# small_tv_screen.net
KiCad netlist of a schematic drawn in EasyEDA Pro
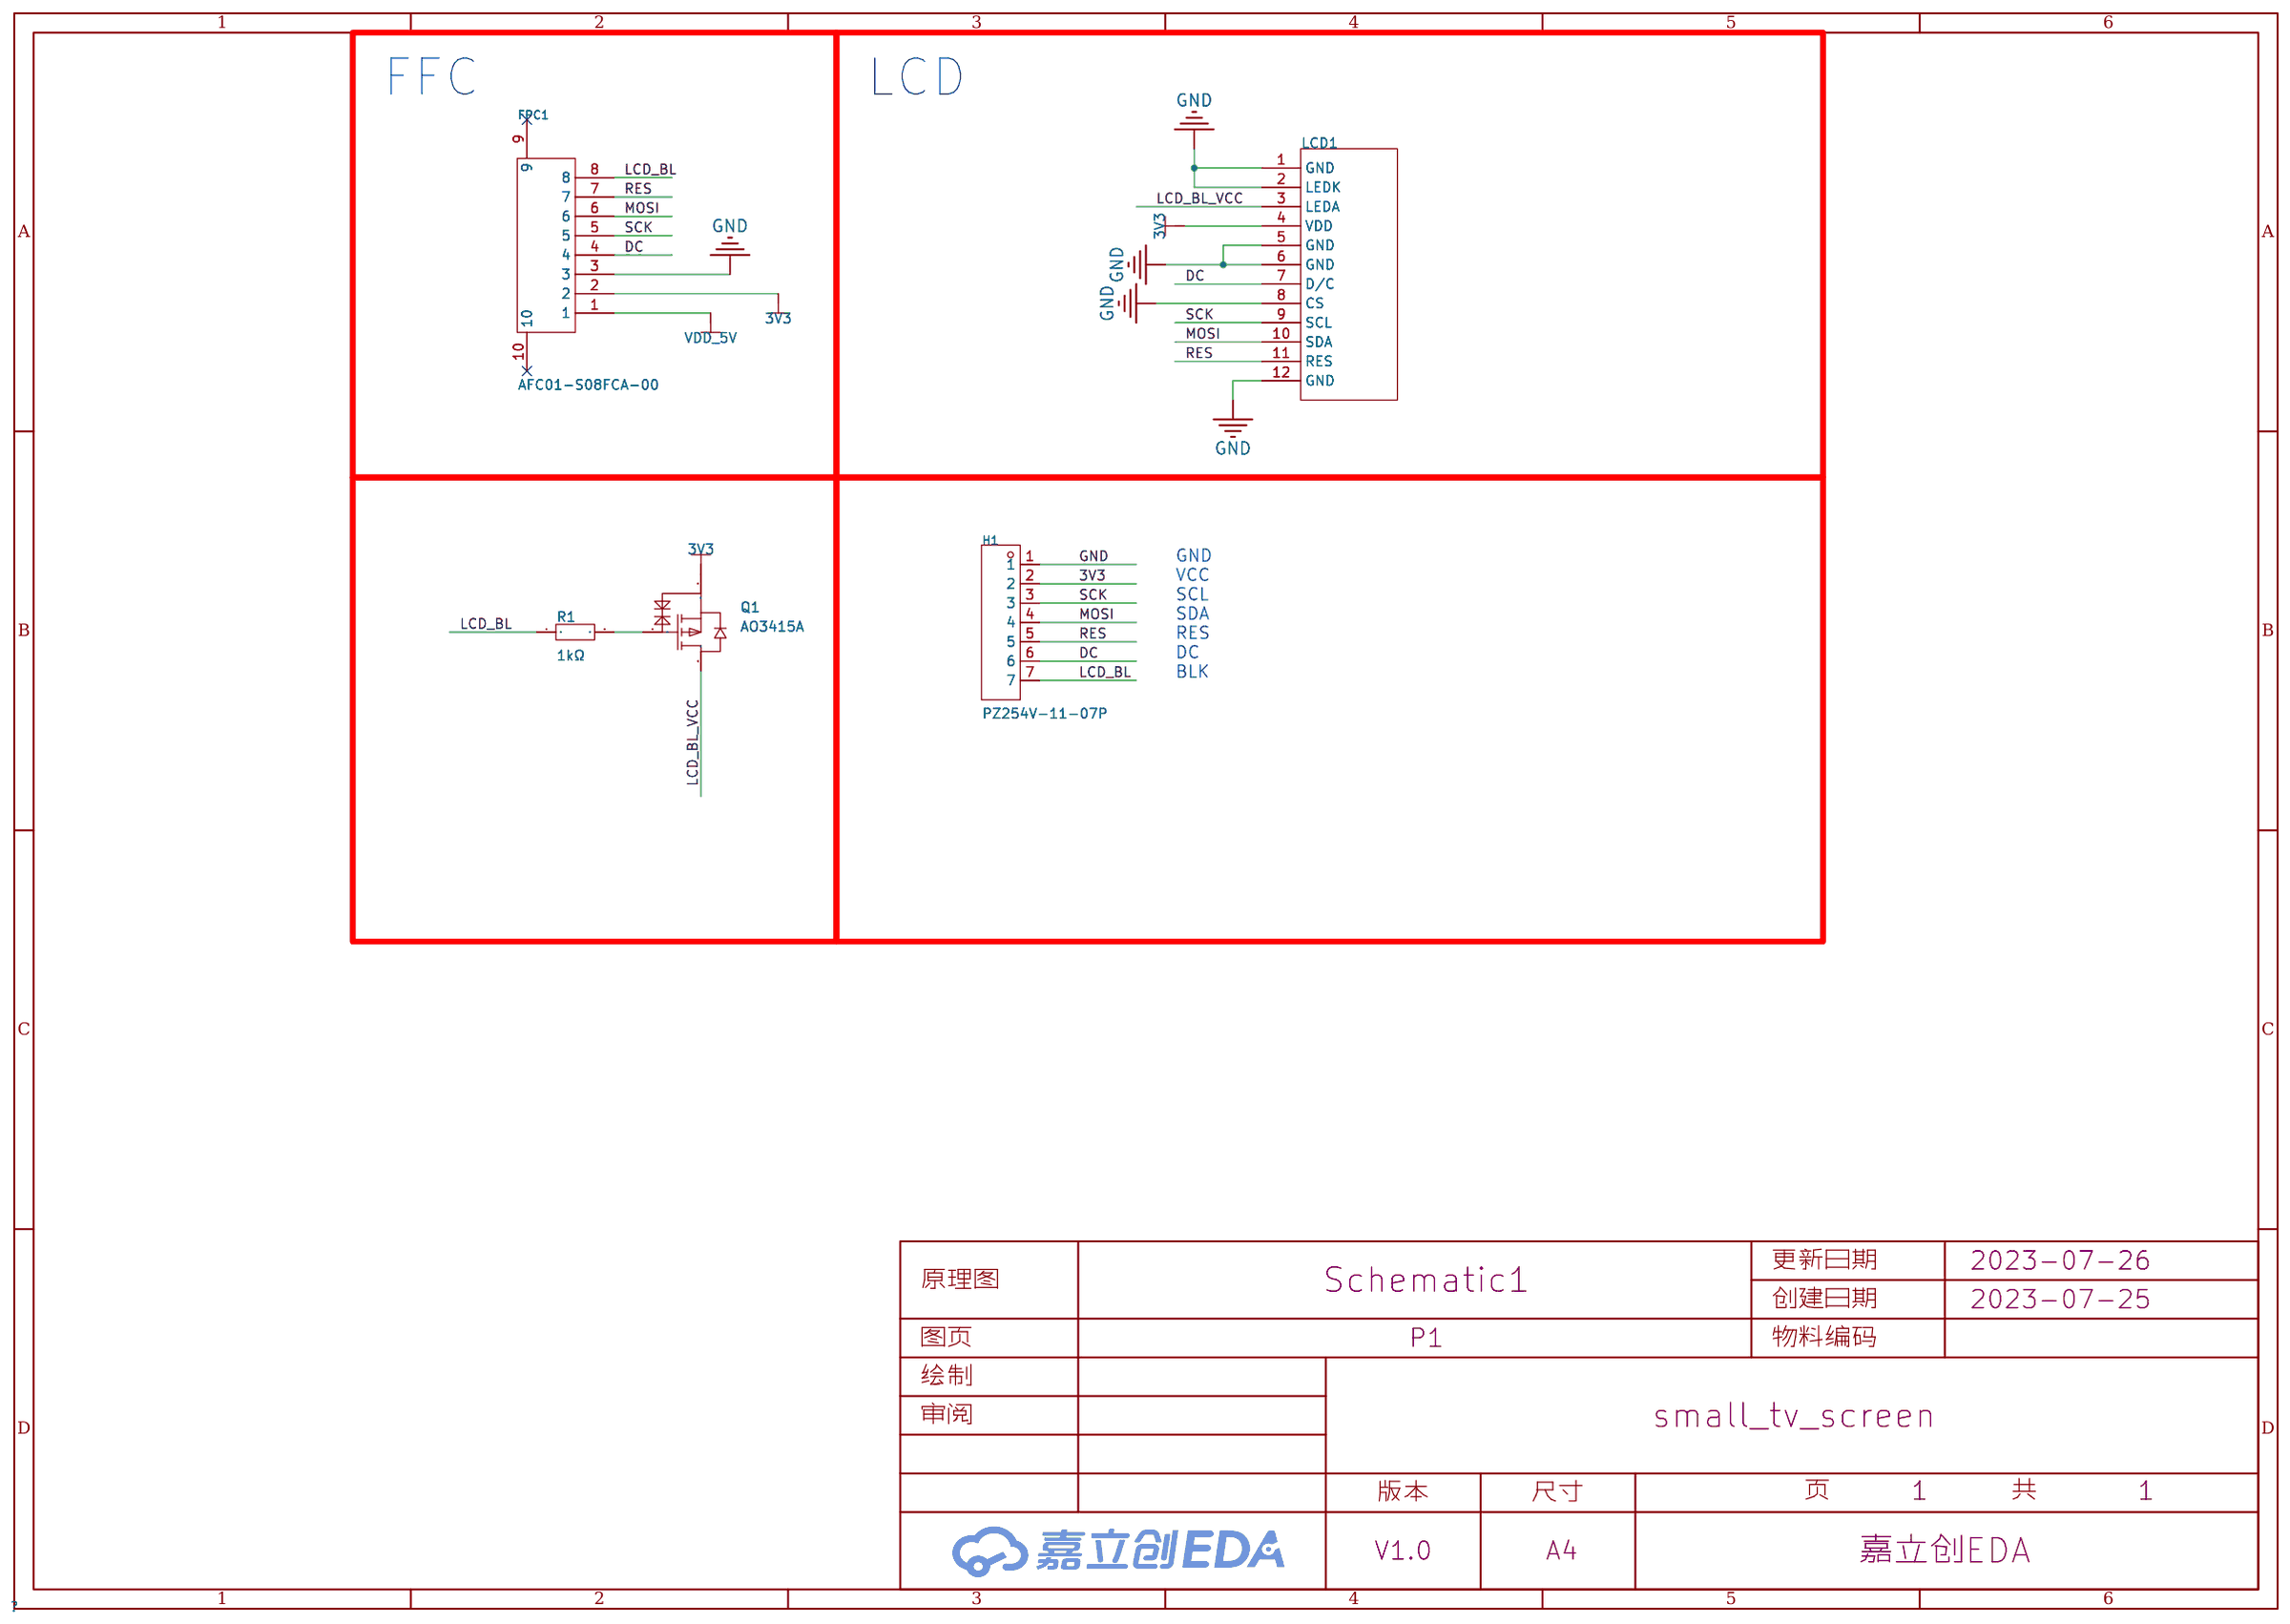
[diagram p0: schematic sheet]

(export (version "E")
  (design (tool "Eeschema 10.0.6"))
  (components
    (comp (ref "FPC1")
      (value "AFC01-S08FCA-00")
      (footprint "easyedapro:FPC-SMD_P0.50-8P_FGS-XJ-H2.0")
      (description "间距:0.5mm;触点数量:8P;锁定特性:翻盖式;安装类型:卧贴;触点类型:下接;")
      (fields (field (name "Manufacturer") "JS(钜硕电子)"))
      (libsource (lib "easyedapro") (part "AFC01-S08FCA-00"))
    )
    (comp (ref "H1")
      (value "PZ254V-11-07P")
      (footprint "easyedapro:HDR-TH_7P-P2.54-V-M")
      (fields (field (name "Manufacturer") "XFCN(兴飞)"))
      (libsource (lib "easyedapro") (part "PZ254V-11-07P"))
    )
    (comp (ref "LCD1") (value "LCD") (libsource (lib "easyedapro") (part "LCD-240X240")))
    (comp (ref "Q1")
      (value "AO3415A")
      (footprint "easyedapro:SOT-23-3_L2.9-W1.6-P1.90-LS2.8-BR")
      (description "类型:P沟道;漏源电压(Vdss):20V;连续漏极电流(Id):5A;功率(Pd):1.5W;导通电阻(RDS(on)@Vgs,Id):45mΩ@4.5V,4A;")
      (fields (field (name "Manufacturer") "AOS"))
      (libsource (lib "easyedapro") (part "AO3415A"))
    )
    (comp (ref "R1")
      (value "1kΩ")
      (footprint "easyedapro:R0603")
      (description "电阻类型:厚膜电阻;阻值:1kΩ;精度:±1%;功率:100mW;")
      (fields
        (field (name "Manufacturer Part") "0603WAF1001T5E")
        (field (name "Manufacturer") "UNI-ROYAL(厚声)")
      )
      (libsource (lib "easyedapro") (part "0603WAF1001T5E"))
    )
  )
  (nets
    (net (code "1") (name "/DC") (class "Default")
      (node (ref "FPC1") (pin "4") (pinfunction "4_4") (pintype "input"))
      (node (ref "H1") (pin "6") (pinfunction "6_6") (pintype "input"))
      (node (ref "LCD1") (pin "7") (pinfunction "D/C_7") (pintype "input"))
    )
    (net (code "2") (name "/LCD_BL") (class "Default")
      (node (ref "FPC1") (pin "8") (pinfunction "8_8") (pintype "input"))
      (node (ref "H1") (pin "7") (pinfunction "7_7") (pintype "input"))
      (node (ref "R1") (pin "1") (pinfunction "1_1") (pintype "input"))
    )
    (net (code "3") (name "/LCD_BL_VCC") (class "Default")
      (node (ref "LCD1") (pin "3") (pinfunction "LEDA_3") (pintype "input"))
      (node (ref "Q1") (pin "3") (pinfunction "D_3") (pintype "input"))
    )
    (net (code "4") (name "/MOSI") (class "Default")
      (node (ref "FPC1") (pin "6") (pinfunction "6_6") (pintype "input"))
      (node (ref "H1") (pin "4") (pinfunction "4_4") (pintype "input"))
      (node (ref "LCD1") (pin "10") (pinfunction "SDA_10") (pintype "input"))
    )
    (net (code "5") (name "/RES") (class "Default")
      (node (ref "FPC1") (pin "7") (pinfunction "7_7") (pintype "input"))
      (node (ref "H1") (pin "5") (pinfunction "5_5") (pintype "input"))
      (node (ref "LCD1") (pin "11") (pinfunction "RES_11") (pintype "input"))
    )
    (net (code "6") (name "/SCK") (class "Default")
      (node (ref "FPC1") (pin "5") (pinfunction "5_5") (pintype "input"))
      (node (ref "H1") (pin "3") (pinfunction "3_3") (pintype "input"))
      (node (ref "LCD1") (pin "9") (pinfunction "SCL_9") (pintype "input"))
    )
    (net (code "7") (name "3V3") (class "Default")
      (node (ref "FPC1") (pin "2") (pinfunction "2_2") (pintype "input"))
      (node (ref "H1") (pin "2") (pinfunction "2_2") (pintype "input"))
      (node (ref "LCD1") (pin "4") (pinfunction "VDD_4") (pintype "input"))
      (node (ref "Q1") (pin "2") (pinfunction "S_2") (pintype "input"))
    )
    (net (code "8") (name "GND") (class "Default")
      (node (ref "FPC1") (pin "3") (pinfunction "3_3") (pintype "input"))
      (node (ref "H1") (pin "1") (pinfunction "1_1") (pintype "input"))
      (node (ref "LCD1") (pin "1") (pinfunction "GND_1") (pintype "input"))
      (node (ref "LCD1") (pin "12") (pinfunction "GND_12") (pintype "input"))
      (node (ref "LCD1") (pin "2") (pinfunction "LEDK_2") (pintype "input"))
      (node (ref "LCD1") (pin "5") (pinfunction "GND_5") (pintype "input"))
      (node (ref "LCD1") (pin "6") (pinfunction "GND_6") (pintype "input"))
      (node (ref "LCD1") (pin "8") (pinfunction "CS_8") (pintype "input"))
    )
    (net (code "9") (name "Net-(Q1-G)") (class "Default")
      (node (ref "Q1") (pin "1") (pinfunction "G_1") (pintype "input"))
      (node (ref "R1") (pin "2") (pinfunction "2_2") (pintype "input"))
    )
    (net (code "10") (name "VDD_5V") (class "Default")
      (node (ref "FPC1") (pin "1") (pinfunction "1_1") (pintype "input"))
    )
    (net (code "11") (name "unconnected-(FPC1-Pad9)") (class "Default")
      (node (ref "FPC1") (pin "9") (pinfunction "9_9") (pintype "input+no_connect"))
    )
    (net (code "12") (name "unconnected-(FPC1-Pad10)") (class "Default")
      (node (ref "FPC1") (pin "10") (pinfunction "10_10") (pintype "input+no_connect"))
    )
  )
)
